# voltage_sensor_HiZ_HV.net
KiCad netlist of a schematic drawn in Altium Designer
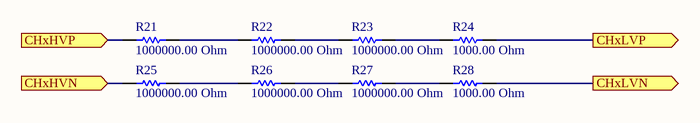
[diagram p0: voltage_sensor_HiZ_HV.SchDoc]

(export (version "E")
  (design (tool "Eeschema 10.0.6"))
  (components
    (comp (ref "R21")
      (value "1000000.00 Ohm")
      (footprint "RESC1206(3216)_L")
      (description "1M 0.25W 1% 1206 (3216 Metric)  SMD")
      (fields (field (name "TOLERANCE") "1 %") (field (name "POWER") "0.25 W"))
      (libsource (lib "Altium Content Vault") (part "RES"))
    )
    (comp (ref "R22")
      (value "1000000.00 Ohm")
      (footprint "RESC1206(3216)_L")
      (description "1M 0.25W 1% 1206 (3216 Metric)  SMD")
      (fields (field (name "TOLERANCE") "1 %") (field (name "POWER") "0.25 W"))
      (libsource (lib "Altium Content Vault") (part "RES"))
    )
    (comp (ref "R23")
      (value "1000000.00 Ohm")
      (footprint "RESC1206(3216)_L")
      (description "1M 0.25W 1% 1206 (3216 Metric)  SMD")
      (fields (field (name "TOLERANCE") "1 %") (field (name "POWER") "0.25 W"))
      (libsource (lib "Altium Content Vault") (part "RES"))
    )
    (comp (ref "R24")
      (value "1000.00 Ohm")
      (footprint "RESC1206(3216)_L")
      (description "1K 0.25W 1% 1206 (3216 Metric)  SMD")
      (fields (field (name "POWER") "0.25 W") (field (name "TOLERANCE") "1 %"))
      (libsource (lib "Altium Content Vault") (part "RES"))
    )
    (comp (ref "R25")
      (value "1000000.00 Ohm")
      (footprint "RESC1206(3216)_L")
      (description "1M 0.25W 1% 1206 (3216 Metric)  SMD")
      (fields (field (name "TOLERANCE") "1 %") (field (name "POWER") "0.25 W"))
      (libsource (lib "Altium Content Vault") (part "RES"))
    )
    (comp (ref "R26")
      (value "1000000.00 Ohm")
      (footprint "RESC1206(3216)_L")
      (description "1M 0.25W 1% 1206 (3216 Metric)  SMD")
      (fields (field (name "TOLERANCE") "1 %") (field (name "POWER") "0.25 W"))
      (libsource (lib "Altium Content Vault") (part "RES"))
    )
    (comp (ref "R27")
      (value "1000000.00 Ohm")
      (footprint "RESC1206(3216)_L")
      (description "1M 0.25W 1% 1206 (3216 Metric)  SMD")
      (fields (field (name "TOLERANCE") "1 %") (field (name "POWER") "0.25 W"))
      (libsource (lib "Altium Content Vault") (part "RES"))
    )
    (comp (ref "R28")
      (value "1000.00 Ohm")
      (footprint "RESC1206(3216)_L")
      (description "1K 0.25W 1% 1206 (3216 Metric)  SMD")
      (fields (field (name "POWER") "0.25 W") (field (name "TOLERANCE") "1 %"))
      (libsource (lib "Altium Content Vault") (part "RES"))
    )
  )
  (nets
    (net (code "1") (name "/CHxHVN") (class "Default")
      (node (ref "R25") (pin "2") (pinfunction "2_2") (pintype "passive"))
    )
    (net (code "2") (name "/CHxHVP") (class "Default")
      (node (ref "R21") (pin "2") (pinfunction "2_2") (pintype "passive"))
    )
    (net (code "3") (name "/CHxLVN") (class "Default")
      (node (ref "R28") (pin "1") (pinfunction "1_1") (pintype "passive"))
    )
    (net (code "4") (name "/CHxLVP") (class "Default")
      (node (ref "R24") (pin "1") (pinfunction "1_1") (pintype "passive"))
    )
    (net (code "5") (name "Net-(R21-Pad1)") (class "Default")
      (node (ref "R21") (pin "1") (pinfunction "1_1") (pintype "passive"))
      (node (ref "R22") (pin "2") (pinfunction "2_2") (pintype "passive"))
    )
    (net (code "6") (name "Net-(R22-Pad1)") (class "Default")
      (node (ref "R22") (pin "1") (pinfunction "1_1") (pintype "passive"))
      (node (ref "R23") (pin "2") (pinfunction "2_2") (pintype "passive"))
    )
    (net (code "7") (name "Net-(R23-Pad1)") (class "Default")
      (node (ref "R23") (pin "1") (pinfunction "1_1") (pintype "passive"))
      (node (ref "R24") (pin "2") (pinfunction "2_2") (pintype "passive"))
    )
    (net (code "8") (name "Net-(R25-Pad1)") (class "Default")
      (node (ref "R25") (pin "1") (pinfunction "1_1") (pintype "passive"))
      (node (ref "R26") (pin "2") (pinfunction "2_2") (pintype "passive"))
    )
    (net (code "9") (name "Net-(R26-Pad1)") (class "Default")
      (node (ref "R26") (pin "1") (pinfunction "1_1") (pintype "passive"))
      (node (ref "R27") (pin "2") (pinfunction "2_2") (pintype "passive"))
    )
    (net (code "10") (name "Net-(R27-Pad1)") (class "Default")
      (node (ref "R27") (pin "1") (pinfunction "1_1") (pintype "passive"))
      (node (ref "R28") (pin "2") (pinfunction "2_2") (pintype "passive"))
    )
  )
)
